# LVDS_repeater.net
KiCad netlist of a schematic drawn in Altium Designer
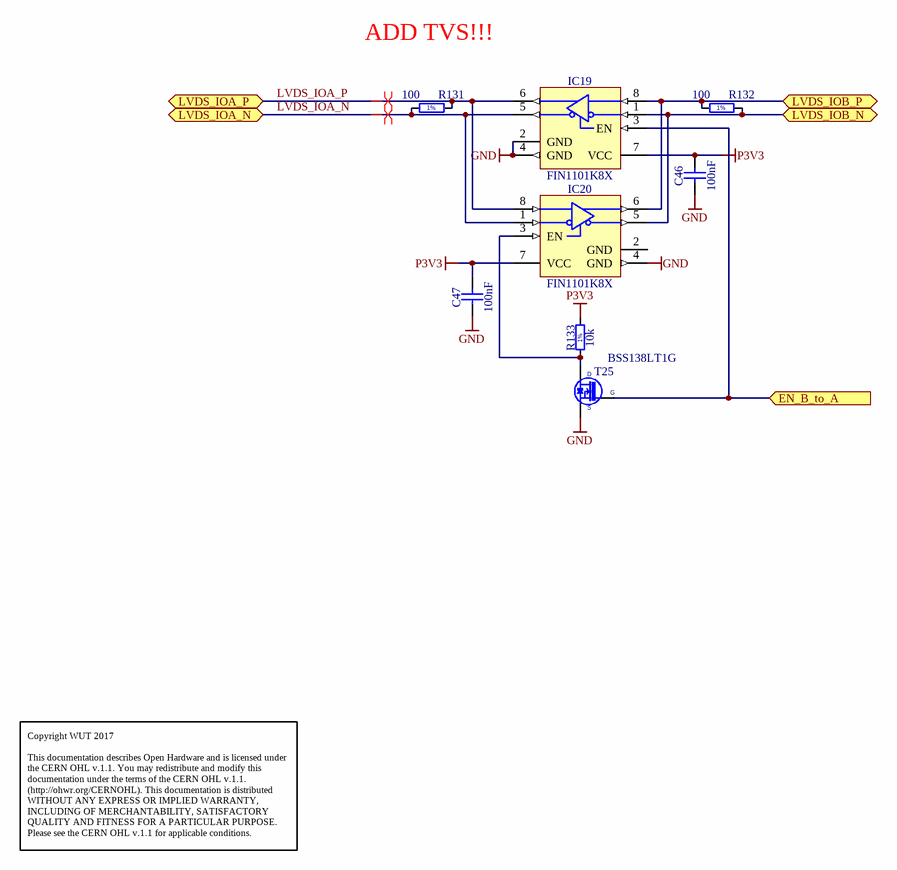
[diagram p0: LVDS_repeater.SchDoc]

(export (version "E")
  (design (tool "Eeschema 10.0.6"))
  (components
    (comp (ref "C46")
      (value "100nF")
      (footprint "CAPC1005X55N")
      (description "Non-polarised capacitor")
      (fields
        (field (name "PART NUMBER") "CC0402_100NF_16V_10%_X5R")
        (field (name "VOLTAGE") "16V")
        (field (name "AUTHOR") "CERN DEM JLC")
      )
      (libsource (lib "Capacitors") (part "Capacitor - non polarized"))
    )
    (comp (ref "C47")
      (value "100nF")
      (footprint "CAPC1005X55N")
      (description "Non-polarised capacitor")
      (fields
        (field (name "PART NUMBER") "CC0402_100NF_16V_10%_X5R")
        (field (name "VOLTAGE") "16V")
        (field (name "AUTHOR") "CERN DEM JLC")
      )
      (libsource (lib "Capacitors") (part "Capacitor - non polarized"))
    )
    (comp (ref "IC19")
      (value "FIN1101K8X")
      (footprint "SOP50P310X90-8N")
      (description "LVDS Single Port High Speed Repeater")
      (fields (field (name "MANUFACTURER") "FAIRCHILD SEMICONDUCTOR") (field (name "AUTHOR") "CERN DEM JLC"))
      (libsource (lib "ICs And Semiconductors") (part "FIN1101K8X"))
    )
    (comp (ref "IC20")
      (value "FIN1101K8X")
      (footprint "SOP50P310X90-8N")
      (description "LVDS Single Port High Speed Repeater")
      (fields (field (name "MANUFACTURER") "FAIRCHILD SEMICONDUCTOR") (field (name "AUTHOR") "CERN DEM JLC"))
      (libsource (lib "") (part "FIN1101K8X_1"))
    )
    (comp (ref "R131")
      (value "100")
      (footprint "RESC1005X40N")
      (description "Resistor - 1%")
      (fields
        (field (name "PART NUMBER") "R0402_100R_1%_0.1W_100PPM")
        (field (name "POWER") "0.1W")
        (field (name "AUTHOR") "CERN DEM JLC")
      )
      (libsource (lib "Resistors") (part "Resistor - 1%"))
    )
    (comp (ref "R132")
      (value "100")
      (footprint "RESC1005X40N")
      (description "Resistor - 1%")
      (fields
        (field (name "PART NUMBER") "R0402_100R_1%_0.1W_100PPM")
        (field (name "POWER") "0.1W")
        (field (name "AUTHOR") "CERN DEM JLC")
      )
      (libsource (lib "Resistors") (part "Resistor - 1%"))
    )
    (comp (ref "R133")
      (value "10k")
      (footprint "RESC1005X40N")
      (description "Resistor - 1%")
      (fields
        (field (name "PART NUMBER") "R0402_10K_1%_0.0625W_100PPM")
        (field (name "POWER") "0.0625W")
        (field (name "AUTHOR") "CERN DEM JLC")
      )
      (libsource (lib "Resistors") (part "Resistor - 1%"))
    )
    (comp (ref "T25")
      (value "BSS138LT1G")
      (footprint "SOT95P240X110-3N")
      (description "N-CHANNEL MOSFET WITH DIODE")
      (fields (field (name "MANUFACTURER") "ON SEMICONDUCTOR") (field (name "AUTHOR") "CERN DEM JLC"))
      (libsource (lib "ICs And Semiconductors") (part "N-MOSFET-D 1G 2S 3D"))
    )
  )
  (nets
    (net (code "1") (name "/EN_B_to_A") (class "Default")
      (node (ref "IC19") (pin "3") (pinfunction "EN_3") (pintype "input"))
      (node (ref "T25") (pin "1") (pinfunction "G_1") (pintype "passive"))
    )
    (net (code "2") (name "/LVDS_IOA_N") (class "Default")
      (node (ref "IC19") (pin "5") (pinfunction "DOUT-_5") (pintype "output"))
      (node (ref "IC20") (pin "1") (pinfunction "RIN-_1") (pintype "input"))
      (node (ref "R131") (pin "1") (pinfunction "1_1") (pintype "passive"))
    )
    (net (code "3") (name "/LVDS_IOA_P") (class "Default")
      (node (ref "IC19") (pin "6") (pinfunction "DOUT+_6") (pintype "output"))
      (node (ref "IC20") (pin "8") (pinfunction "RIN+_8") (pintype "input"))
      (node (ref "R131") (pin "2") (pinfunction "2_2") (pintype "passive"))
    )
    (net (code "4") (name "/LVDS_IOB_N") (class "Default")
      (node (ref "IC19") (pin "1") (pinfunction "RIN-_1") (pintype "input"))
      (node (ref "IC20") (pin "5") (pinfunction "DOUT-_5") (pintype "output"))
      (node (ref "R132") (pin "2") (pinfunction "2_2") (pintype "passive"))
    )
    (net (code "5") (name "/LVDS_IOB_P") (class "Default")
      (node (ref "IC19") (pin "8") (pinfunction "RIN+_8") (pintype "input"))
      (node (ref "IC20") (pin "6") (pinfunction "DOUT+_6") (pintype "output"))
      (node (ref "R132") (pin "1") (pinfunction "1_1") (pintype "passive"))
    )
    (net (code "6") (name "GND") (class "Default")
      (node (ref "C46") (pin "1") (pinfunction "1_1") (pintype "passive"))
      (node (ref "C47") (pin "1") (pinfunction "1_1") (pintype "passive"))
      (node (ref "IC19") (pin "2") (pinfunction "GND_2") (pintype "power_in"))
      (node (ref "IC19") (pin "4") (pinfunction "GND_4") (pintype "output"))
      (node (ref "IC20") (pin "4") (pinfunction "GND_4") (pintype "output"))
      (node (ref "T25") (pin "2") (pinfunction "S_2") (pintype "passive"))
    )
    (net (code "7") (name "Net-(IC20-EN)") (class "Default")
      (node (ref "IC20") (pin "3") (pinfunction "EN_3") (pintype "input"))
      (node (ref "R133") (pin "1") (pinfunction "1_1") (pintype "passive"))
      (node (ref "T25") (pin "3") (pinfunction "D_3") (pintype "passive"))
    )
    (net (code "8") (name "P3V3") (class "Default")
      (node (ref "C46") (pin "2") (pinfunction "2_2") (pintype "passive"))
      (node (ref "C47") (pin "2") (pinfunction "2_2") (pintype "passive"))
      (node (ref "IC19") (pin "7") (pinfunction "VCC_7") (pintype "power_in"))
      (node (ref "IC20") (pin "7") (pinfunction "VCC_7") (pintype "power_in"))
      (node (ref "R133") (pin "2") (pinfunction "2_2") (pintype "passive"))
    )
    (net (code "9") (name "unconnected-(IC20-GND-Pad2)") (class "Default")
      (node (ref "IC20") (pin "2") (pinfunction "GND_2") (pintype "power_in"))
    )
  )
)
